# CATS-Vega-Baro.net
KiCad netlist of a schematic drawn in Altium Designer
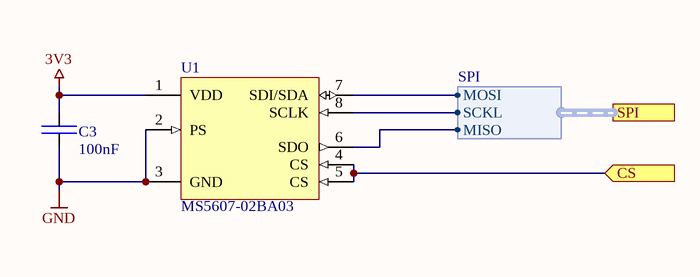
[diagram p0: CATS-Vega-Baro.SchDoc]

(export (version "E")
  (design (tool "Eeschema 10.0.6"))
  (components
    (comp (ref "C3")
      (value "100nF")
      (footprint "SMD Keramikkondensator 0603")
      (description "SMD Ceramic Capacitor E6")
      (libsource (lib "CATS-EUROC") (part "E6 - 100nF"))
    )
    (comp (ref "U1")
      (value "MS5607-02BA03")
      (footprint "SMD IC BARO MS5607")
      (description "Barometric Pressure Sensor, with stainless\r\nsteel cap")
      (libsource (lib "Sensors") (part "MS5607-02BA03"))
    )
  )
  (nets
    (net (code "2") (name "/CS") (class "Default")
      (node (ref "U1") (pin "4") (pinfunction "CS_4") (pintype "input"))
      (node (ref "U1") (pin "5") (pinfunction "CS_5") (pintype "input"))
    )
    (net (code "3") (name "/MISO") (class "Default")
      (node (ref "U1") (pin "6") (pinfunction "SDO_6") (pintype "output"))
    )
    (net (code "4") (name "/MOSI") (class "Default")
      (node (ref "U1") (pin "7") (pinfunction "SDI/SDA_7") (pintype "bidirectional"))
    )
    (net (code "5") (name "/SCKL") (class "Default")
      (node (ref "U1") (pin "8") (pinfunction "SCLK_8") (pintype "input"))
    )
    (net (code "7") (name "3V3") (class "Default")
      (node (ref "C3") (pin "2") (pinfunction "2_2") (pintype "passive"))
      (node (ref "U1") (pin "1") (pinfunction "VDD_1") (pintype "passive"))
    )
    (net (code "8") (name "GND") (class "Default")
      (node (ref "C3") (pin "1") (pinfunction "1_1") (pintype "passive"))
      (node (ref "U1") (pin "2") (pinfunction "PS_2") (pintype "input"))
      (node (ref "U1") (pin "3") (pinfunction "GND_3") (pintype "passive"))
    )
  )
)
